# openSX70_ALPHA_V6_3-20181010.net
KiCad netlist of a schematic drawn in EAGLE
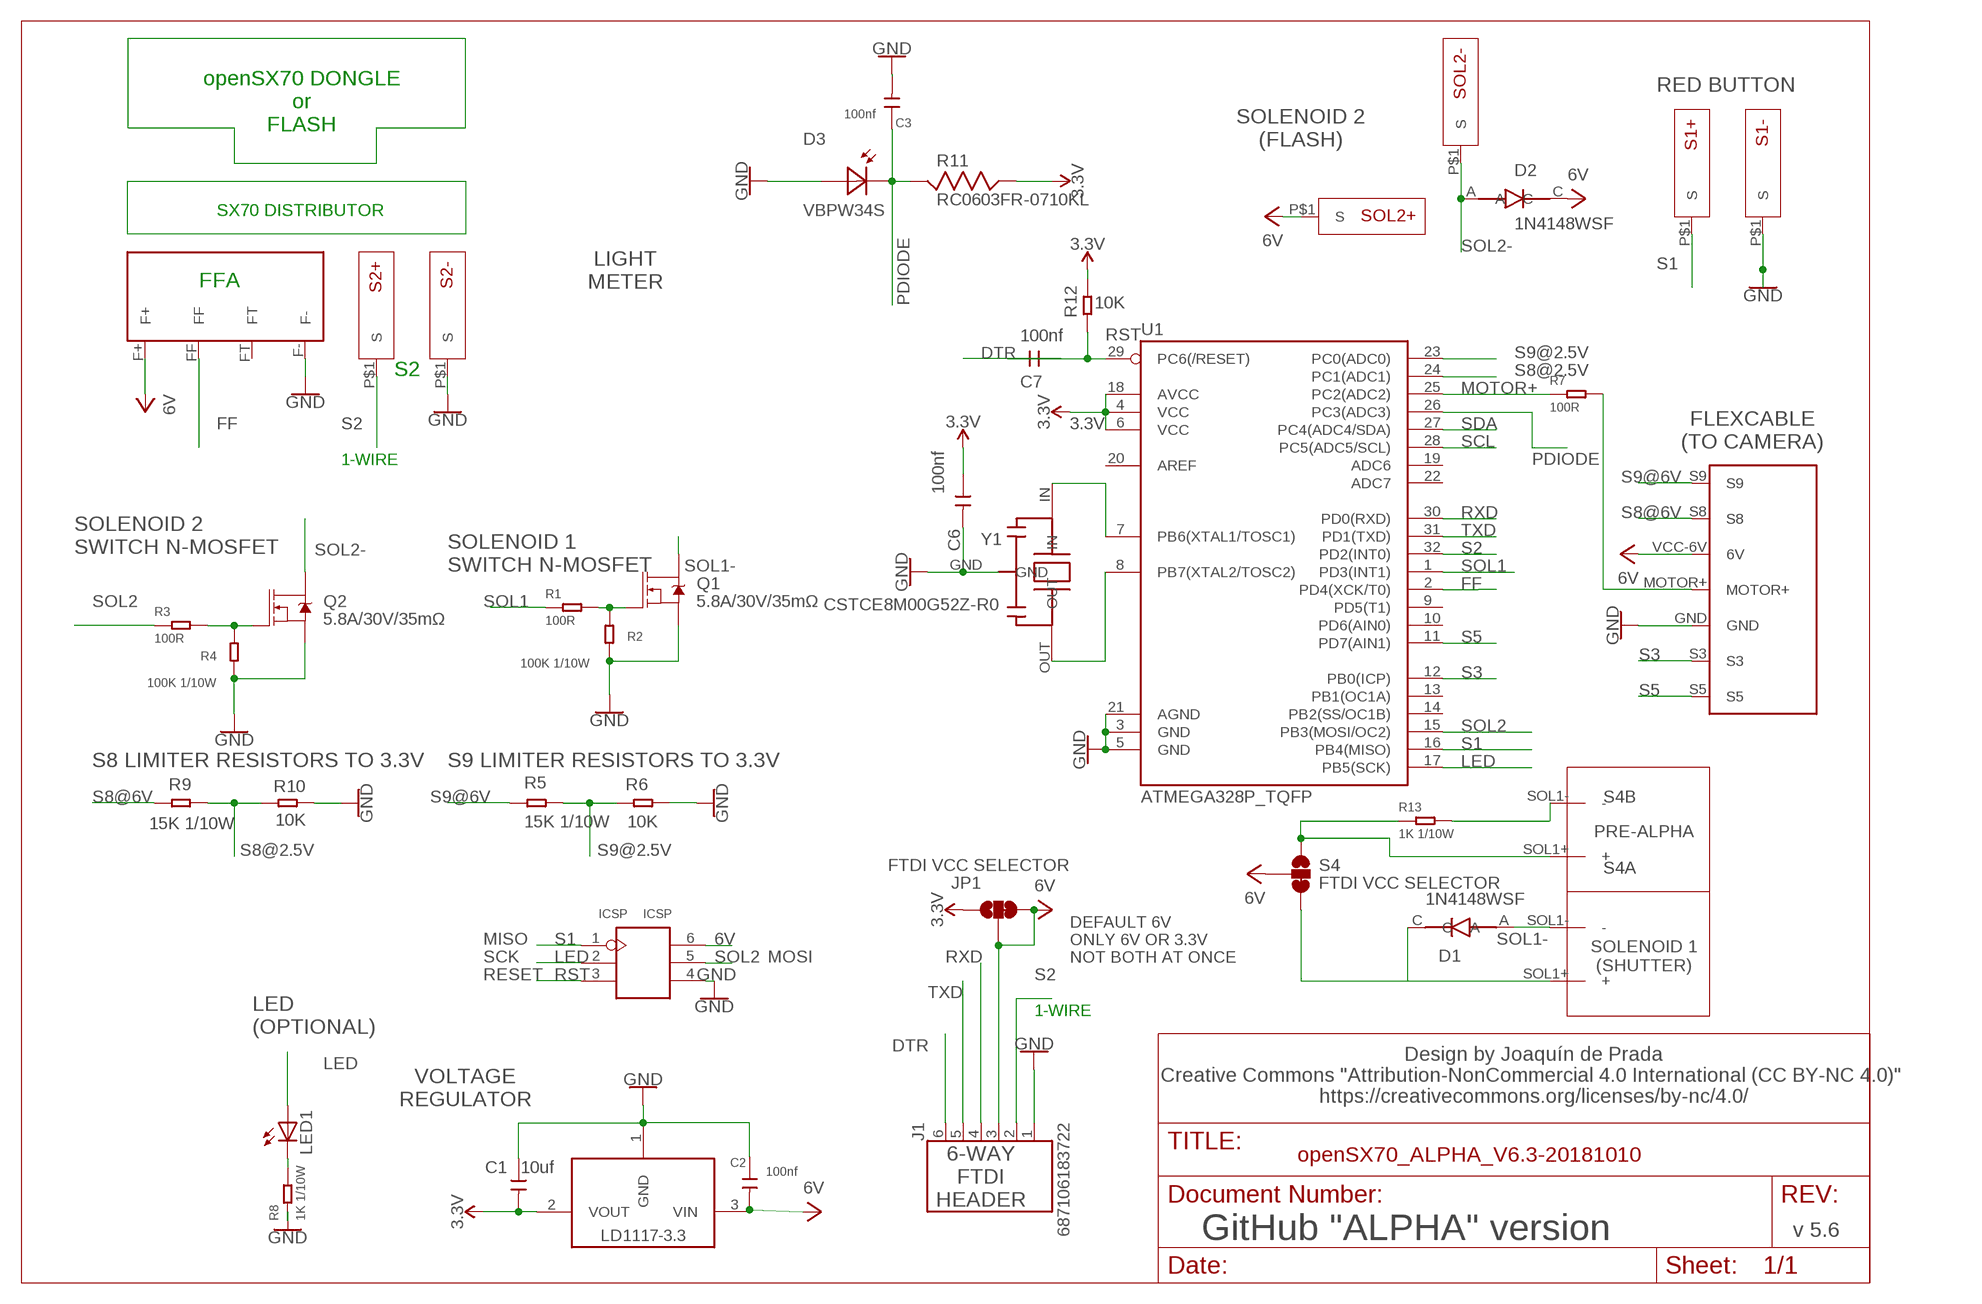
[diagram p0: schematic, sheet 1]

(export (version "E")
  (design (tool "Eeschema 10.0.6"))
  (components
    (comp (ref "C1")
      (value "10uf")
      (footprint "eagle-import:C0603")
      (fields (field (name "MPN") "CC0603KRX5R6BB106"))
      (libsource (lib "eagle-import") (part "CERAMIC-10UF-10V-10%-X5R(0603)"))
    )
    (comp (ref "C2")
      (value "100nf")
      (footprint "eagle-import:C0603")
      (fields (field (name "MPN") "CC0603KRX7R9BB104"))
      (libsource (lib "eagle-import") (part "CERAMIC-100NF-50V-10%-X7R(0603)"))
    )
    (comp (ref "C3")
      (value "100nf")
      (footprint "eagle-import:C0603")
      (fields (field (name "MPN") "CC0603KRX7R9BB104"))
      (libsource (lib "eagle-import") (part "CERAMIC-100NF-50V-10%-X7R(0603)"))
    )
    (comp (ref "C6")
      (value "100nf")
      (footprint "eagle-import:C0603")
      (fields (field (name "MPN") "CC0603KRX7R9BB104"))
      (libsource (lib "eagle-import") (part "CERAMIC-100NF-50V-10%-X7R(0603)"))
    )
    (comp (ref "C7")
      (value "100nf")
      (footprint "eagle-import:C0603")
      (fields (field (name "MPN") "CC0603KRX7R9BB104"))
      (libsource (lib "eagle-import") (part "CERAMIC-100NF-50V-10%-X7R(0603)"))
    )
    (comp (ref "D1")
      (value "1N4148WSF")
      (footprint "eagle-import:SODFL2512X100N")
      (fields (field (name "MANUFACTURER") "Fairchild Semiconductor"))
      (libsource (lib "eagle-import") (part "1N4148WS"))
    )
    (comp (ref "D2")
      (value "1N4148WSF")
      (footprint "eagle-import:SODFL2512X100N")
      (fields (field (name "MANUFACTURER") "Fairchild Semiconductor"))
      (libsource (lib "eagle-import") (part "1N4148WS"))
    )
    (comp (ref "D3")
      (value "VBPW34S")
      (footprint "eagle-import:SOD6439X130N")
      (fields (field (name "DIGI-KEY_PART_NUMBER") "751-1500-1-ND") (field (name "MF") "Vishay"))
      (libsource (lib "eagle-import") (part "VBPW34S"))
    )
    (comp (ref "ICSP")
      (value "ICSP")
      (footprint "eagle-import:H2X3-2.54")
      (libsource (lib "eagle-import") (part "ICSP"))
    )
    (comp (ref "J1")
      (value "687106183722")
      (footprint "eagle-import:687106183722")
      (fields (field (name "MF") "Wurth Electronics"))
      (libsource (lib "eagle-import") (part "687106183722"))
    )
    (comp (ref "JP1")
      (value "FTDI VCC SELECTOR")
      (footprint "eagle-import:SMT-JUMPER_3_1-NC_TRACE_SILK")
      (libsource (lib "eagle-import") (part "JUMPER-SMT_3_1-NC_TRACE_SILK"))
    )
    (comp (ref "LD11172.5V")
      (value "LD1117 2.5V")
      (footprint "eagle-import:SOT223")
      (fields (field (name "MF") "Advanced Monolithic Systems") (field (name "MP") "AMS1117-5.0"))
      (libsource (lib "eagle-import") (part "LD1117-3.3"))
    )
    (comp (ref "LED1")
      (value "LEDCHIPLED_0805")
      (footprint "eagle-import:CHIPLED_0805")
      (libsource (lib "eagle-import") (part "LEDCHIPLED_0805"))
    )
    (comp (ref "Q1")
      (value "5.8A/30V/35mΩ")
      (footprint "eagle-import:SOT23-3")
      (libsource (lib "eagle-import") (part "MOSFET-NCH-AO3404A"))
    )
    (comp (ref "Q2")
      (value "5.8A/30V/35mΩ")
      (footprint "eagle-import:SOT23-3")
      (libsource (lib "eagle-import") (part "MOSFET-NCH-AO3404A"))
    )
    (comp (ref "R1")
      (value "100R")
      (footprint "eagle-import:R0603")
      (fields (field (name "MPN") "RC0603JR-07100RL"))
      (libsource (lib "eagle-import") (part "SMD-RES-100R-5%-1/10W(0603)"))
    )
    (comp (ref "R2")
      (value "100K 1/10W")
      (footprint "eagle-import:R0603")
      (fields (field (name "MPN") "RC0603JR-07100KL"))
      (libsource (lib "eagle-import") (part "SMD-RES-100K-5%-1/10W(0603)"))
    )
    (comp (ref "R3")
      (value "100R")
      (footprint "eagle-import:R0603")
      (fields (field (name "MPN") "RC0603JR-07100RL"))
      (libsource (lib "eagle-import") (part "SMD-RES-100R-5%-1/10W(0603)"))
    )
    (comp (ref "R4")
      (value "100K 1/10W")
      (footprint "eagle-import:R0603")
      (fields (field (name "MPN") "RC0603JR-07100KL"))
      (libsource (lib "eagle-import") (part "SMD-RES-100K-5%-1/10W(0603)"))
    )
    (comp (ref "R5")
      (value "15K 1/10W")
      (footprint "eagle-import:R0603")
      (fields (field (name "MPN") "RC0603FR-0715KL"))
      (libsource (lib "eagle-import") (part "SMD-RES-15K-1%-1/10W(0603)"))
    )
    (comp (ref "R6")
      (value "10K")
      (footprint "eagle-import:R0603")
      (fields (field (name "MPN") "RC0603FR-0710KL"))
      (libsource (lib "eagle-import") (part "SMD-RES-10K-1%-1/10W(0603)"))
    )
    (comp (ref "R7")
      (value "100R")
      (footprint "eagle-import:R0603")
      (fields (field (name "MPN") "RC0603JR-07100RL"))
      (libsource (lib "eagle-import") (part "SMD-RES-100R-5%-1/10W(0603)"))
    )
    (comp (ref "R8")
      (value "1K 1/10W")
      (footprint "eagle-import:R0603")
      (fields (field (name "MPN") "RC0603JR-071KL"))
      (libsource (lib "eagle-import") (part "SMD-RES-1K-5%-1/10W(0603)"))
    )
    (comp (ref "R9")
      (value "15K 1/10W")
      (footprint "eagle-import:R0603")
      (fields (field (name "MPN") "RC0603FR-0715KL"))
      (libsource (lib "eagle-import") (part "SMD-RES-15K-1%-1/10W(0603)"))
    )
    (comp (ref "R10")
      (value "10K")
      (footprint "eagle-import:R0603")
      (fields (field (name "MPN") "RC0603FR-0710KL"))
      (libsource (lib "eagle-import") (part "SMD-RES-10K-1%-1/10W(0603)"))
    )
    (comp (ref "R11")
      (value "RC0603FR-0710KL")
      (footprint "eagle-import:RC0603FR-0710KL_RESC1608X55")
      (fields (field (name "MANUFACTURER") "YAGEO"))
      (libsource (lib "eagle-import") (part "RC0603FR-0710KL"))
    )
    (comp (ref "R12")
      (value "10K")
      (footprint "eagle-import:R0603")
      (fields (field (name "MPN") "RC0603FR-0710KL"))
      (libsource (lib "eagle-import") (part "SMD-RES-10K-1%-1/10W(0603)"))
    )
    (comp (ref "R13")
      (value "1K 1/10W")
      (footprint "eagle-import:R0603")
      (fields (field (name "MPN") "RC0603JR-071KL"))
      (libsource (lib "eagle-import") (part "SMD-RES-1K-5%-1/10W(0603)"))
    )
    (comp (ref "S1+")
      (value "SX70-S-PAD-NEW")
      (footprint "eagle-import:SX70-S-PAD2")
      (libsource (lib "eagle-import") (part "SX70-S-PAD-NEW"))
    )
    (comp (ref "S1-")
      (value "SX70-S-PAD-NEW")
      (footprint "eagle-import:SX70-S-PAD2")
      (libsource (lib "eagle-import") (part "SX70-S-PAD-NEW"))
    )
    (comp (ref "S2+")
      (value "SX70-S-PAD-NEW")
      (footprint "eagle-import:SX70-S-PAD2")
      (libsource (lib "eagle-import") (part "SX70-S-PAD-NEW"))
    )
    (comp (ref "S2-")
      (value "SX70-S-PAD-NEW")
      (footprint "eagle-import:SX70-S-PAD2")
      (libsource (lib "eagle-import") (part "SX70-S-PAD-NEW"))
    )
    (comp (ref "S4")
      (value "FTDI VCC SELECTOR")
      (footprint "eagle-import:SMT-JUMPER_3_1-NC_TRACE_SILK")
      (libsource (lib "eagle-import") (part "JUMPER-SMT_3_1-NC_TRACE_SILK"))
    )
    (comp (ref "SOL1")
      (value "SX70-SOLENOID1-2PADS")
      (footprint "eagle-import:SX70-SOLENOID1-2")
      (libsource (lib "eagle-import") (part "SX70-SOLENOID1-2PADS"))
    )
    (comp (ref "SOL2")
      (value "SX70-SOLENOID1-2PADS")
      (footprint "eagle-import:SX70-SOLENOID1-2")
      (libsource (lib "eagle-import") (part "SX70-SOLENOID1-2PADS"))
    )
    (comp (ref "SOL2+")
      (value "SX70-S-PAD-NEW")
      (footprint "eagle-import:SX70-S-PAD2")
      (libsource (lib "eagle-import") (part "SX70-S-PAD-NEW"))
    )
    (comp (ref "SOL2-")
      (value "SX70-S-PAD-NEW")
      (footprint "eagle-import:SX70-S-PAD2")
      (libsource (lib "eagle-import") (part "SX70-S-PAD-NEW"))
    )
    (comp (ref "U$1")
      (value "SX70-7-PAD")
      (footprint "eagle-import:SX70-7-PAD")
      (libsource (lib "eagle-import") (part "SX70-7-PAD"))
    )
    (comp (ref "U$2")
      (value "FFA")
      (footprint "eagle-import:FFA-PAD-PACKAGE")
      (libsource (lib "eagle-import") (part "SX70-FFA-PAD"))
    )
    (comp (ref "U1")
      (value "ATMEGA328P_TQFP")
      (footprint "eagle-import:TQFP32-08")
      (libsource (lib "eagle-import") (part "ATMEGA328P_TQFP"))
    )
    (comp (ref "Y1")
      (value "CSTCE8M00G52Z-R0")
      (footprint "eagle-import:CFP95P160X100-3N")
      (fields (field (name "MF") "Murata") (field (name "MP") "CSTCE16M0V53-R0"))
      (libsource (lib "eagle-import") (part "CSTCE16M0V53-R0"))
    )
  )
  (nets
    (net (code "1") (name "/DTR") (class "Default")
      (node (ref "C7") (pin "1") (pinfunction "1_1") (pintype "passive"))
      (node (ref "J1") (pin "6") (pinfunction "1_6") (pintype "passive"))
    )
    (net (code "2") (name "/FF") (class "Default")
      (node (ref "U$2") (pin "FF") (pinfunction "FF_FF") (pintype "bidirectional"))
      (node (ref "U1") (pin "2") (pinfunction "PD4(XCK/T0)_2") (pintype "bidirectional"))
    )
    (net (code "3") (name "/LED") (class "Default")
      (node (ref "ICSP") (pin "2") (pinfunction "SCK_2") (pintype "bidirectional"))
      (node (ref "LED1") (pin "A") (pinfunction "A_A") (pintype "passive"))
      (node (ref "U1") (pin "17") (pinfunction "PB5(SCK)_17") (pintype "bidirectional"))
    )
    (net (code "4") (name "/MOTOR+") (class "Default")
      (node (ref "R7") (pin "1") (pinfunction "1_1") (pintype "passive"))
      (node (ref "U1") (pin "25") (pinfunction "PC2(ADC2)_25") (pintype "bidirectional"))
    )
    (net (code "5") (name "/PDIODE") (class "Default")
      (node (ref "C3") (pin "1") (pinfunction "1_1") (pintype "passive"))
      (node (ref "D3") (pin "C") (pinfunction "C_C") (pintype "passive"))
      (node (ref "R11") (pin "1") (pinfunction "1_1") (pintype "passive"))
      (node (ref "U1") (pin "26") (pinfunction "PC3(ADC3)_26") (pintype "bidirectional"))
    )
    (net (code "6") (name "/RST") (class "Default")
      (node (ref "C7") (pin "2") (pinfunction "2_2") (pintype "passive"))
      (node (ref "ICSP") (pin "3") (pinfunction "RST_3") (pintype "bidirectional"))
      (node (ref "R12") (pin "1") (pinfunction "1_1") (pintype "passive"))
      (node (ref "U1") (pin "29") (pinfunction "PC6(/RESET)_29") (pintype "bidirectional"))
    )
    (net (code "7") (name "/RXD") (class "Default")
      (node (ref "J1") (pin "4") (pinfunction "3_4") (pintype "passive"))
      (node (ref "U1") (pin "30") (pinfunction "PD0(RXD)_30") (pintype "bidirectional"))
    )
    (net (code "8") (name "/S1") (class "Default")
      (node (ref "ICSP") (pin "1") (pinfunction "MISO_1") (pintype "bidirectional"))
      (node (ref "S1+") (pin "P$1") (pinfunction "S_P$1") (pintype "bidirectional"))
      (node (ref "U1") (pin "16") (pinfunction "PB4(MISO)_16") (pintype "bidirectional"))
    )
    (net (code "9") (name "/S2") (class "Default")
      (node (ref "J1") (pin "2") (pinfunction "5_2") (pintype "passive"))
      (node (ref "S2+") (pin "P$1") (pinfunction "S_P$1") (pintype "bidirectional"))
      (node (ref "U1") (pin "32") (pinfunction "PD2(INT0)_32") (pintype "bidirectional"))
    )
    (net (code "10") (name "/S3") (class "Default")
      (node (ref "U$1") (pin "S3") (pinfunction "S3_S3") (pintype "bidirectional"))
      (node (ref "U1") (pin "12") (pinfunction "PB0(ICP)_12") (pintype "bidirectional"))
    )
    (net (code "11") (name "/S5") (class "Default")
      (node (ref "U$1") (pin "S5") (pinfunction "S5_S5") (pintype "bidirectional"))
      (node (ref "U1") (pin "11") (pinfunction "PD7(AIN1)_11") (pintype "bidirectional"))
    )
    (net (code "12") (name "/S8@2.5V") (class "Default")
      (node (ref "R10") (pin "1") (pinfunction "1_1") (pintype "passive"))
      (node (ref "R9") (pin "2") (pinfunction "2_2") (pintype "passive"))
      (node (ref "U1") (pin "24") (pinfunction "PC1(ADC1)_24") (pintype "bidirectional"))
    )
    (net (code "13") (name "/S8@6V") (class "Default")
      (node (ref "R9") (pin "1") (pinfunction "1_1") (pintype "passive"))
      (node (ref "U$1") (pin "S8") (pinfunction "S8_S8") (pintype "bidirectional"))
    )
    (net (code "14") (name "/S9@2.5V") (class "Default")
      (node (ref "R5") (pin "2") (pinfunction "2_2") (pintype "passive"))
      (node (ref "R6") (pin "1") (pinfunction "1_1") (pintype "passive"))
      (node (ref "U1") (pin "23") (pinfunction "PC0(ADC0)_23") (pintype "bidirectional"))
    )
    (net (code "15") (name "/S9@6V") (class "Default")
      (node (ref "R5") (pin "1") (pinfunction "1_1") (pintype "passive"))
      (node (ref "U$1") (pin "S9") (pinfunction "S9_S9") (pintype "bidirectional"))
    )
    (net (code "16") (name "/SCL") (class "Default")
      (node (ref "U1") (pin "28") (pinfunction "PC5(ADC5/SCL)_28") (pintype "bidirectional"))
    )
    (net (code "17") (name "/SDA") (class "Default")
      (node (ref "U1") (pin "27") (pinfunction "PC4(ADC4/SDA)_27") (pintype "bidirectional"))
    )
    (net (code "18") (name "/SOL1") (class "Default")
      (node (ref "R1") (pin "1") (pinfunction "1_1") (pintype "passive"))
      (node (ref "U1") (pin "1") (pinfunction "PD3(INT1)_1") (pintype "bidirectional"))
    )
    (net (code "19") (name "/SOL1-") (class "Default")
      (node (ref "D1") (pin "A") (pinfunction "A_A") (pintype "passive"))
      (node (ref "Q1") (pin "3") (pinfunction "D_3") (pintype "bidirectional"))
      (node (ref "SOL1") (pin "SOL1-") (pinfunction "-_SOL1-") (pintype "bidirectional"))
    )
    (net (code "20") (name "/SOL2") (class "Default")
      (node (ref "ICSP") (pin "5") (pinfunction "MOSI_5") (pintype "bidirectional"))
      (node (ref "R3") (pin "1") (pinfunction "1_1") (pintype "passive"))
      (node (ref "U1") (pin "15") (pinfunction "PB3(MOSI/OC2)_15") (pintype "bidirectional"))
    )
    (net (code "21") (name "/SOL2-") (class "Default")
      (node (ref "D2") (pin "A") (pinfunction "A_A") (pintype "passive"))
      (node (ref "Q2") (pin "3") (pinfunction "D_3") (pintype "bidirectional"))
      (node (ref "SOL2-") (pin "P$1") (pinfunction "S_P$1") (pintype "bidirectional"))
    )
    (net (code "22") (name "/TXD") (class "Default")
      (node (ref "J1") (pin "5") (pinfunction "2_5") (pintype "passive"))
      (node (ref "U1") (pin "31") (pinfunction "PD1(TXD)_31") (pintype "bidirectional"))
    )
    (net (code "23") (name "3.3V") (class "Default")
      (node (ref "C1") (pin "2") (pinfunction "2_2") (pintype "passive"))
      (node (ref "C6") (pin "1") (pinfunction "1_1") (pintype "passive"))
      (node (ref "JP1") (pin "1") (pinfunction "1_1") (pintype "passive"))
      (node (ref "LD11172.5V") (pin "2") (pinfunction "VOUT_2") (pintype "bidirectional"))
      (node (ref "R11") (pin "2") (pinfunction "2_2") (pintype "passive"))
      (node (ref "R12") (pin "2") (pinfunction "2_2") (pintype "passive"))
      (node (ref "U1") (pin "18") (pinfunction "AVCC_18") (pintype "bidirectional"))
      (node (ref "U1") (pin "4") (pinfunction "VCC_4") (pintype "bidirectional"))
      (node (ref "U1") (pin "6") (pinfunction "VCC_6") (pintype "bidirectional"))
    )
    (net (code "24") (name "6V") (class "Default")
      (node (ref "C2") (pin "2") (pinfunction "2_2") (pintype "passive"))
      (node (ref "D2") (pin "C") (pinfunction "C_C") (pintype "passive"))
      (node (ref "ICSP") (pin "6") (pinfunction "VCC_6") (pintype "bidirectional"))
      (node (ref "J1") (pin "3") (pinfunction "4_3") (pintype "passive"))
      (node (ref "JP1") (pin "2") (pinfunction "2_2") (pintype "passive"))
      (node (ref "JP1") (pin "3") (pinfunction "3_3") (pintype "passive"))
      (node (ref "LD11172.5V") (pin "3") (pinfunction "VIN_3") (pintype "bidirectional"))
      (node (ref "S4") (pin "2") (pinfunction "2_2") (pintype "passive"))
      (node (ref "SOL2+") (pin "P$1") (pinfunction "S_P$1") (pintype "bidirectional"))
      (node (ref "U$1") (pin "VCC-6V") (pinfunction "6V_VCC-6V") (pintype "bidirectional"))
      (node (ref "U$2") (pin "F+") (pinfunction "F+_F+") (pintype "bidirectional"))
    )
    (net (code "25") (name "GND") (class "Default")
      (node (ref "C1") (pin "1") (pinfunction "1_1") (pintype "passive"))
      (node (ref "C2") (pin "1") (pinfunction "1_1") (pintype "passive"))
      (node (ref "C3") (pin "2") (pinfunction "2_2") (pintype "passive"))
      (node (ref "C6") (pin "2") (pinfunction "2_2") (pintype "passive"))
      (node (ref "D3") (pin "A") (pinfunction "A_A") (pintype "passive"))
      (node (ref "ICSP") (pin "4") (pinfunction "GND_4") (pintype "bidirectional"))
      (node (ref "J1") (pin "1") (pinfunction "6_1") (pintype "passive"))
      (node (ref "LD11172.5V") (pin "1") (pinfunction "GND_1") (pintype "bidirectional"))
      (node (ref "Q1") (pin "2") (pinfunction "S_2") (pintype "bidirectional"))
      (node (ref "Q2") (pin "2") (pinfunction "S_2") (pintype "bidirectional"))
      (node (ref "R10") (pin "2") (pinfunction "2_2") (pintype "passive"))
      (node (ref "R2") (pin "1") (pinfunction "1_1") (pintype "passive"))
      (node (ref "R4") (pin "1") (pinfunction "1_1") (pintype "passive"))
      (node (ref "R6") (pin "2") (pinfunction "2_2") (pintype "passive"))
      (node (ref "R8") (pin "1") (pinfunction "1_1") (pintype "passive"))
      (node (ref "S1-") (pin "P$1") (pinfunction "S_P$1") (pintype "bidirectional"))
      (node (ref "S2-") (pin "P$1") (pinfunction "S_P$1") (pintype "bidirectional"))
      (node (ref "U$1") (pin "GND") (pinfunction "GND_GND") (pintype "bidirectional"))
      (node (ref "U$2") (pin "F-") (pinfunction "F-_F-") (pintype "bidirectional"))
      (node (ref "U1") (pin "21") (pinfunction "AGND_21") (pintype "bidirectional"))
      (node (ref "U1") (pin "3") (pinfunction "GND_3") (pintype "bidirectional"))
      (node (ref "U1") (pin "5") (pinfunction "GND_5") (pintype "bidirectional"))
      (node (ref "Y1") (pin "GND") (pinfunction "GND_GND") (pintype "passive"))
    )
    (net (code "26") (name "Net-(LED1-PadC)") (class "Default")
      (node (ref "LED1") (pin "C") (pinfunction "C_C") (pintype "passive"))
      (node (ref "R8") (pin "2") (pinfunction "2_2") (pintype "passive"))
    )
    (net (code "27") (name "Net-(Q1-G)") (class "Default")
      (node (ref "Q1") (pin "1") (pinfunction "G_1") (pintype "bidirectional"))
      (node (ref "R1") (pin "2") (pinfunction "2_2") (pintype "passive"))
      (node (ref "R2") (pin "2") (pinfunction "2_2") (pintype "passive"))
    )
    (net (code "28") (name "Net-(Q2-G)") (class "Default")
      (node (ref "Q2") (pin "1") (pinfunction "G_1") (pintype "bidirectional"))
      (node (ref "R3") (pin "2") (pinfunction "2_2") (pintype "passive"))
      (node (ref "R4") (pin "2") (pinfunction "2_2") (pintype "passive"))
    )
    (net (code "29") (name "Net-(R7-Pad2)") (class "Default")
      (node (ref "R7") (pin "2") (pinfunction "2_2") (pintype "passive"))
      (node (ref "U$1") (pin "MOTOR+") (pinfunction "MOTOR+_MOTOR+") (pintype "bidirectional"))
    )
    (net (code "30") (name "Net-(SOL1-+)") (class "Default")
      (node (ref "D1") (pin "C") (pinfunction "C_C") (pintype "passive"))
      (node (ref "S4") (pin "3") (pinfunction "3_3") (pintype "passive"))
      (node (ref "SOL1") (pin "SOL1+") (pinfunction "+_SOL1+") (pintype "bidirectional"))
    )
    (net (code "31") (name "Net-(SOL2-+)") (class "Default")
      (node (ref "R13") (pin "1") (pinfunction "1_1") (pintype "passive"))
      (node (ref "S4") (pin "1") (pinfunction "1_1") (pintype "passive"))
      (node (ref "SOL2") (pin "SOL1+") (pinfunction "+_SOL1+") (pintype "bidirectional"))
    )
    (net (code "32") (name "Net-(SOL2--)") (class "Default")
      (node (ref "R13") (pin "2") (pinfunction "2_2") (pintype "passive"))
      (node (ref "SOL2") (pin "SOL1-") (pinfunction "-_SOL1-") (pintype "bidirectional"))
    )
    (net (code "33") (name "Net-(U1-PB6(XTAL1{slash}TOSC1))") (class "Default")
      (node (ref "U1") (pin "7") (pinfunction "PB6(XTAL1/TOSC1)_7") (pintype "bidirectional"))
      (node (ref "Y1") (pin "IN") (pinfunction "IN_IN") (pintype "input"))
    )
    (net (code "34") (name "Net-(U1-PB7(XTAL2{slash}TOSC2))") (class "Default")
      (node (ref "U1") (pin "8") (pinfunction "PB7(XTAL2/TOSC2)_8") (pintype "bidirectional"))
      (node (ref "Y1") (pin "OUT") (pinfunction "OUT_OUT") (pintype "output"))
    )
    (net (code "35") (name "unconnected-(U$2-PadFT)") (class "Default")
      (node (ref "U$2") (pin "FT") (pinfunction "FT_FT") (pintype "bidirectional"))
    )
    (net (code "36") (name "unconnected-(U1-ADC6-Pad19)") (class "Default")
      (node (ref "U1") (pin "19") (pinfunction "ADC6_19") (pintype "bidirectional"))
    )
    (net (code "37") (name "unconnected-(U1-ADC7-Pad22)") (class "Default")
      (node (ref "U1") (pin "22") (pinfunction "ADC7_22") (pintype "bidirectional"))
    )
    (net (code "38") (name "unconnected-(U1-AREF-Pad20)") (class "Default")
      (node (ref "U1") (pin "20") (pinfunction "AREF_20") (pintype "bidirectional"))
    )
    (net (code "39") (name "unconnected-(U1-PB1(OC1A)-Pad13)") (class "Default")
      (node (ref "U1") (pin "13") (pinfunction "PB1(OC1A)_13") (pintype "bidirectional"))
    )
    (net (code "40") (name "unconnected-(U1-PB2(SS{slash}OC1B)-Pad14)") (class "Default")
      (node (ref "U1") (pin "14") (pinfunction "PB2(SS/OC1B)_14") (pintype "bidirectional"))
    )
    (net (code "41") (name "unconnected-(U1-PD5(T1)-Pad9)") (class "Default")
      (node (ref "U1") (pin "9") (pinfunction "PD5(T1)_9") (pintype "bidirectional"))
    )
    (net (code "42") (name "unconnected-(U1-PD6(AIN0)-Pad10)") (class "Default")
      (node (ref "U1") (pin "10") (pinfunction "PD6(AIN0)_10") (pintype "bidirectional"))
    )
  )
)
